# Spike_and_Hold.net
KiCad netlist of a schematic drawn in Altium Designer
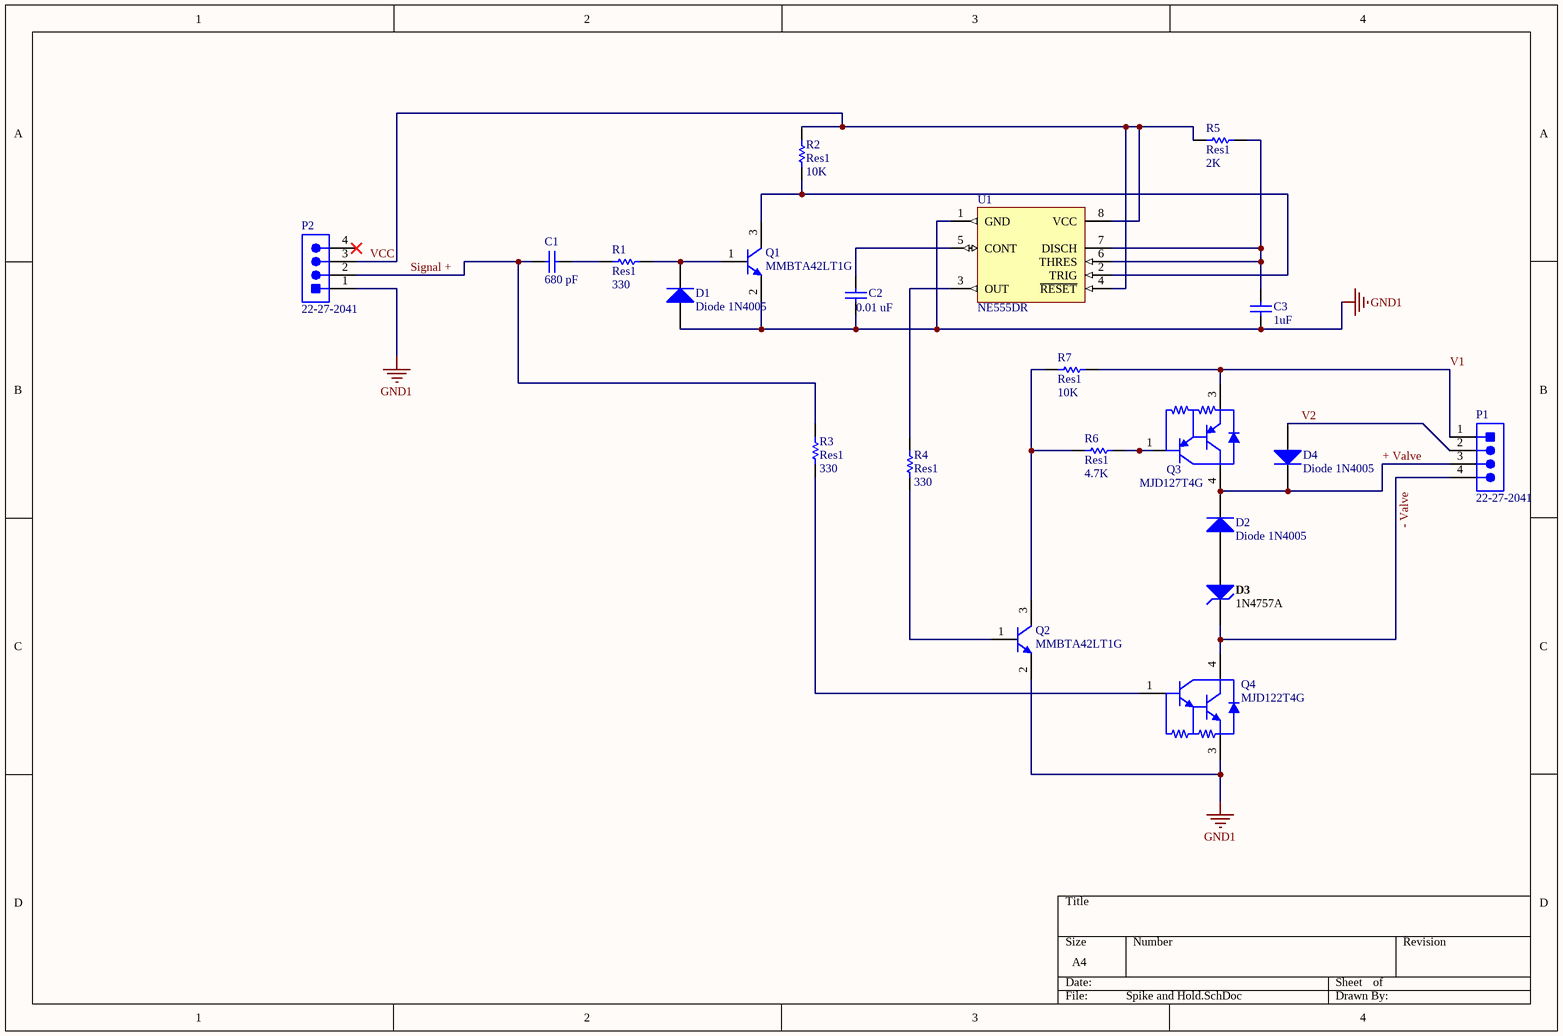
[diagram p0: Spike and Hold.SchDoc]

(export (version "E")
  (design (tool "Eeschema 10.0.6"))
  (components
    (comp (ref "C1")
      (value "680 pF")
      (footprint "CAPC1005X55X30LL05T10")
      (fields (field (name "PART NUMBER") "C0402C681K5RACTU") (field (name "MANUFACTURER") "Kemet"))
      (libsource (lib "Altium Content Vault") (part "CAP"))
    )
    (comp (ref "C2")
      (value "0.01 uF")
      (footprint "CAPC1608X87X35LL15T15")
      (fields (field (name "PART NUMBER") "C0603C103K5RACTU") (field (name "MANUFACTURER") "Kemet"))
      (libsource (lib "Altium Content Vault") (part "CMP-2006-03044-1"))
    )
    (comp (ref "C3")
      (value "1uF")
      (footprint "CAPC1206(3216)110_L")
      (description "CAP 1uF 50V ±10% 1206 (3216 Metric) Thickness 1.1mm SMD")
      (fields (field (name "TOLERANCE") "Â±10%"))
      (libsource (lib "Altium Content Vault") (part "CAP"))
    )
    (comp (ref "D1")
      (value "Diode 1N4005")
      (footprint "DO-41")
      (description "1 Amp General Purpose Rectifier")
      (fields (field (name "PUBLISHER") "Altium Limited"))
      (libsource (lib "Miscellaneous Devices") (part "Diode 1N4005"))
    )
    (comp (ref "D2")
      (value "Diode 1N4005")
      (footprint "DO-41")
      (description "1 Amp General Purpose Rectifier")
      (fields (field (name "PUBLISHER") "Altium Limited"))
      (libsource (lib "Miscellaneous Devices") (part "Diode 1N4005"))
    )
    (comp (ref "D3")
      (value "1N4757A")
      (footprint "FAIR-DO-41-2_V")
      (description "Zener Diode, 51V, 1W, 5%, -65 to 200 degC, 2-Pin DO-41, Body 2.72 x 5.2 mm, RoHS")
      (fields (field (name "MANUFACTURER") "Fairchild Semiconductor") (field (name "TOLERANCE") "5%"))
      (libsource (lib "Altium Content Vault") (part "FAIR-DZEN-A1K2-2"))
    )
    (comp (ref "D4")
      (value "Diode 1N4005")
      (footprint "DO-41")
      (description "1 Amp General Purpose Rectifier")
      (fields (field (name "PUBLISHER") "Altium Limited"))
      (libsource (lib "Miscellaneous Devices") (part "Diode 1N4005"))
    )
    (comp (ref "P1")
      (value "22-27-2041")
      (footprint "MOLX-22-27-2041_V")
      (description "Male Header, Pitch 2.54 mm, 1 x 4 Position, Height 11.7 mm, Tail Length 3.56 mm, RoHS, Bulk")
      (fields (field (name "MANUFACTURER") "Molex"))
      (libsource (lib "Altium Content Vault") (part "CN-1P-M-R4"))
    )
    (comp (ref "P2")
      (value "22-27-2041")
      (footprint "MOLX-22-27-2041_V")
      (description "Male Header, Pitch 2.54 mm, 1 x 4 Position, Height 11.7 mm, Tail Length 3.56 mm, RoHS, Bulk")
      (fields (field (name "MANUFACTURER") "Molex"))
      (libsource (lib "") (part "CN-1P-M-R4_1"))
    )
    (comp (ref "Q1")
      (value "MMBTA42LT1G")
      (footprint "ONSC-SOT-23-3-318-08_V")
      (description "High Voltage Transistor, NPN Silicon, 3-Pin SOT-23, Pb-Free, Tape and Reel")
      (fields (field (name "MANUFACTURER") "On Semiconductor"))
      (libsource (lib "Altium Content Vault") (part "CMP-1048-00662-1"))
    )
    (comp (ref "Q2")
      (value "MMBTA42LT1G")
      (footprint "ONSC-SOT-23-3-318-08_V")
      (description "High Voltage Transistor, NPN Silicon, 3-Pin SOT-23, Pb-Free, Tape and Reel")
      (fields (field (name "MANUFACTURER") "On Semiconductor"))
      (libsource (lib "Altium Content Vault") (part "CMP-1048-00662-1"))
    )
    (comp (ref "Q3")
      (value "MJD127T4G")
      (footprint "ONSC-DPAK-3-369C-01_V")
      (description "Complementary Darlington Power Transistor, 3-Pin DPAK, Pb-Free, Tape and Reel")
      (fields (field (name "MANUFACTURER") "On Semiconductor"))
      (libsource (lib "Altium Content Vault") (part "CMP-1047-00009-1"))
    )
    (comp (ref "Q4")
      (value "MJD122T4G")
      (footprint "ONSC-DPAK-3-369C-01_V")
      (description "Complementary Darlington Power Transistor, 3-Pin DPAK, Pb-Free, Tape and Reel")
      (fields (field (name "MANUFACTURER") "On Semiconductor"))
      (libsource (lib "Altium Content Vault") (part "CMP-1047-00007-1"))
    )
    (comp (ref "R1")
      (value "Res1")
      (footprint "AXIAL-0.3")
      (description "Resistor")
      (fields (field (name "ALTIUM_VALUE") "330") (field (name "PUBLISHER") "Altium Limited"))
      (libsource (lib "Miscellaneous Devices") (part "Res1"))
    )
    (comp (ref "R2")
      (value "Res1")
      (footprint "AXIAL-0.3")
      (description "Resistor")
      (fields (field (name "ALTIUM_VALUE") "10K") (field (name "PUBLISHER") "Altium Limited"))
      (libsource (lib "Miscellaneous Devices") (part "Res1"))
    )
    (comp (ref "R3")
      (value "Res1")
      (footprint "AXIAL-0.3")
      (description "Resistor")
      (fields (field (name "ALTIUM_VALUE") "330") (field (name "PUBLISHER") "Altium Limited"))
      (libsource (lib "Miscellaneous Devices") (part "Res1"))
    )
    (comp (ref "R4")
      (value "Res1")
      (footprint "AXIAL-0.3")
      (description "Resistor")
      (fields (field (name "ALTIUM_VALUE") "330") (field (name "PUBLISHER") "Altium Limited"))
      (libsource (lib "Miscellaneous Devices") (part "Res1"))
    )
    (comp (ref "R5")
      (value "Res1")
      (footprint "AXIAL-0.3")
      (description "Resistor")
      (fields (field (name "ALTIUM_VALUE") "2K") (field (name "PUBLISHER") "Altium Limited"))
      (libsource (lib "Miscellaneous Devices") (part "Res1"))
    )
    (comp (ref "R6")
      (value "Res1")
      (footprint "AXIAL-0.3")
      (description "Resistor")
      (fields (field (name "ALTIUM_VALUE") "4.7K") (field (name "PUBLISHER") "Altium Limited"))
      (libsource (lib "Miscellaneous Devices") (part "Res1"))
    )
    (comp (ref "R7")
      (value "Res1")
      (footprint "AXIAL-0.3")
      (description "Resistor")
      (fields (field (name "ALTIUM_VALUE") "10K") (field (name "PUBLISHER") "Altium Limited"))
      (libsource (lib "Miscellaneous Devices") (part "Res1"))
    )
    (comp (ref "U1")
      (value "NE555DR")
      (footprint "D0008A_L")
      (libsource (lib "Altium Content Vault") (part "CMP-1685-00007-1"))
    )
  )
  (nets
    (net (code "1") (name "/+ Valve") (class "Default")
      (node (ref "D2") (pin "2") (pinfunction "K_2") (pintype "passive"))
      (node (ref "D4") (pin "2") (pinfunction "K_2") (pintype "passive"))
      (node (ref "P1") (pin "3") (pinfunction "3_3") (pintype "passive"))
      (node (ref "Q3") (pin "4") (pinfunction "C_4") (pintype "passive"))
    )
    (net (code "2") (name "/- Valve") (class "Default")
      (node (ref "D3") (pin "2") (pinfunction "K_2") (pintype "passive"))
      (node (ref "P1") (pin "4") (pinfunction "4_4") (pintype "passive"))
      (node (ref "Q4") (pin "4") (pinfunction "C_4") (pintype "passive"))
    )
    (net (code "3") (name "/Signal +") (class "Default")
      (node (ref "C1") (pin "1") (pinfunction "1_1") (pintype "passive"))
      (node (ref "P2") (pin "2") (pinfunction "2_2") (pintype "passive"))
      (node (ref "R3") (pin "2") (pinfunction "2_2") (pintype "passive"))
    )
    (net (code "4") (name "/V1") (class "Default")
      (node (ref "P1") (pin "1") (pinfunction "1_1") (pintype "passive"))
      (node (ref "Q3") (pin "3") (pinfunction "E_3") (pintype "passive"))
      (node (ref "R7") (pin "2") (pinfunction "2_2") (pintype "passive"))
    )
    (net (code "5") (name "/V2") (class "Default")
      (node (ref "D4") (pin "1") (pinfunction "A_1") (pintype "passive"))
      (node (ref "P1") (pin "2") (pinfunction "2_2") (pintype "passive"))
    )
    (net (code "6") (name "/VCC") (class "Default")
      (node (ref "P2") (pin "3") (pinfunction "3_3") (pintype "passive"))
      (node (ref "R2") (pin "2") (pinfunction "2_2") (pintype "passive"))
      (node (ref "R5") (pin "1") (pinfunction "1_1") (pintype "passive"))
      (node (ref "U1") (pin "4") (pinfunction "~{RESET}_4") (pintype "input"))
      (node (ref "U1") (pin "8") (pinfunction "VCC_8") (pintype "power_in"))
    )
    (net (code "7") (name "GND1") (class "Default")
      (node (ref "C2") (pin "1") (pinfunction "1_1") (pintype "passive"))
      (node (ref "C3") (pin "1") (pinfunction "1_1") (pintype "passive"))
      (node (ref "D1") (pin "1") (pinfunction "A_1") (pintype "passive"))
      (node (ref "P2") (pin "1") (pinfunction "1_1") (pintype "passive"))
      (node (ref "Q1") (pin "2") (pinfunction "E_2") (pintype "passive"))
      (node (ref "Q2") (pin "2") (pinfunction "E_2") (pintype "passive"))
      (node (ref "Q4") (pin "3") (pinfunction "E_3") (pintype "passive"))
      (node (ref "U1") (pin "1") (pinfunction "GND_1") (pintype "output"))
    )
    (net (code "8") (name "Net-(C1-Pad2)") (class "Default")
      (node (ref "C1") (pin "2") (pinfunction "2_2") (pintype "passive"))
      (node (ref "R1") (pin "1") (pinfunction "1_1") (pintype "passive"))
    )
    (net (code "9") (name "Net-(D1-K)") (class "Default")
      (node (ref "D1") (pin "2") (pinfunction "K_2") (pintype "passive"))
      (node (ref "Q1") (pin "1") (pinfunction "B_1") (pintype "passive"))
      (node (ref "R1") (pin "2") (pinfunction "2_2") (pintype "passive"))
    )
    (net (code "10") (name "Net-(D2-A)") (class "Default")
      (node (ref "D2") (pin "1") (pinfunction "A_1") (pintype "passive"))
      (node (ref "D3") (pin "1") (pinfunction "A_1") (pintype "passive"))
    )
    (net (code "11") (name "Net-(Q1-C)") (class "Default")
      (node (ref "Q1") (pin "3") (pinfunction "C_3") (pintype "passive"))
      (node (ref "R2") (pin "1") (pinfunction "1_1") (pintype "passive"))
      (node (ref "U1") (pin "2") (pinfunction "TRIG_2") (pintype "input"))
    )
    (net (code "12") (name "Net-(Q2-B)") (class "Default")
      (node (ref "Q2") (pin "1") (pinfunction "B_1") (pintype "passive"))
      (node (ref "R4") (pin "1") (pinfunction "1_1") (pintype "passive"))
    )
    (net (code "13") (name "Net-(Q2-C)") (class "Default")
      (node (ref "Q2") (pin "3") (pinfunction "C_3") (pintype "passive"))
      (node (ref "R6") (pin "1") (pinfunction "1_1") (pintype "passive"))
      (node (ref "R7") (pin "1") (pinfunction "1_1") (pintype "passive"))
    )
    (net (code "14") (name "Net-(Q3-B)") (class "Default")
      (node (ref "Q3") (pin "1") (pinfunction "B_1") (pintype "passive"))
      (node (ref "R6") (pin "2") (pinfunction "2_2") (pintype "passive"))
    )
    (net (code "15") (name "Net-(Q4-B)") (class "Default")
      (node (ref "Q4") (pin "1") (pinfunction "B_1") (pintype "passive"))
      (node (ref "R3") (pin "1") (pinfunction "1_1") (pintype "passive"))
    )
    (net (code "16") (name "Net-(U1-CONT)") (class "Default")
      (node (ref "C2") (pin "2") (pinfunction "2_2") (pintype "passive"))
      (node (ref "U1") (pin "5") (pinfunction "CONT_5") (pintype "bidirectional"))
    )
    (net (code "17") (name "Net-(U1-DISCH)") (class "Default")
      (node (ref "C3") (pin "2") (pinfunction "2_2") (pintype "passive"))
      (node (ref "R5") (pin "2") (pinfunction "2_2") (pintype "passive"))
      (node (ref "U1") (pin "6") (pinfunction "THRES_6") (pintype "input"))
      (node (ref "U1") (pin "7") (pinfunction "DISCH_7") (pintype "open_collector"))
    )
    (net (code "18") (name "Net-(U1-OUT)") (class "Default")
      (node (ref "R4") (pin "2") (pinfunction "2_2") (pintype "passive"))
      (node (ref "U1") (pin "3") (pinfunction "OUT_3") (pintype "output"))
    )
    (net (code "19") (name "unconnected-(P2-Pad4)") (class "Default")
      (node (ref "P2") (pin "4") (pinfunction "4_4") (pintype "passive+no_connect"))
    )
  )
)
